# 04_POWER.net
KiCad netlist of a schematic drawn in Altium Designer
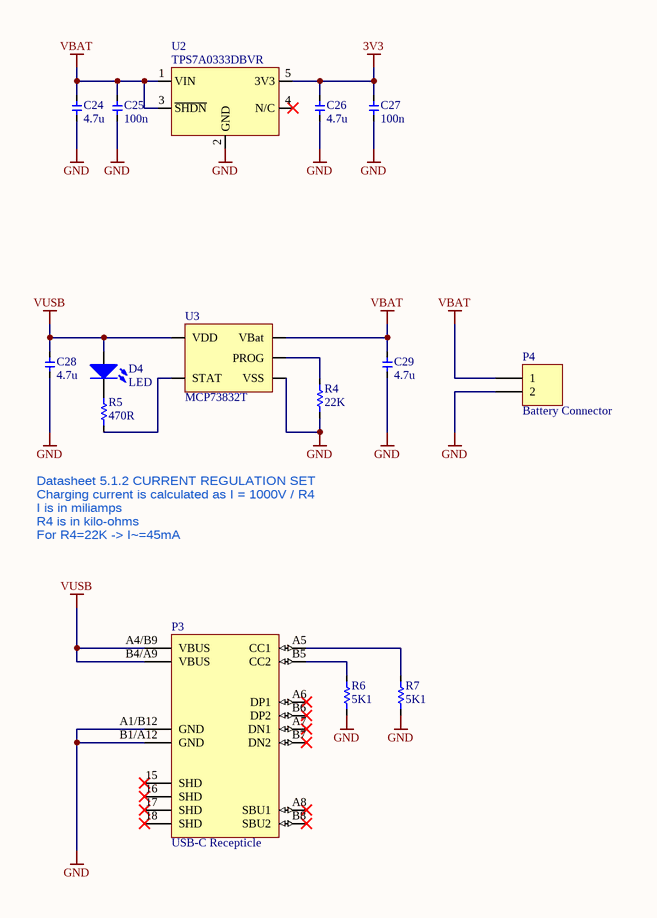
[diagram p0: 04_POWER.SchDoc]

(export (version "E")
  (design (tool "Eeschema 10.0.6"))
  (components
    (comp (ref "C24")
      (value "4.7u")
      (footprint "Moji Footprintovi:0603 - CAP HS")
      (description "Capacitor")
      (fields
        (field (name "MANUFACTURER") "Samsung Electro-Mechanics")
        (field (name "MANUFACTURER PART NUMBER") "CL10B475KQ8NQNC")
      )
      (libsource (lib "Moji Schematici (1)") (part "Cap"))
    )
    (comp (ref "C25")
      (value "100n")
      (footprint "Moji Footprintovi:0603 - CAP HS")
      (description "Capacitor")
      (fields
        (field (name "MANUFACTURER") "Samsung Electro-Mechanics")
        (field (name "MANUFACTURER PART NUMBER") "CL10B104KB8NNWC")
      )
      (libsource (lib "Moji Schematici (1)") (part "Cap"))
    )
    (comp (ref "C26")
      (value "4.7u")
      (footprint "Moji Footprintovi:0603 - CAP HS")
      (description "Capacitor")
      (fields
        (field (name "MANUFACTURER") "Samsung Electro-Mechanics")
        (field (name "MANUFACTURER PART NUMBER") "CL10B475KQ8NQNC")
      )
      (libsource (lib "Moji Schematici (1)") (part "Cap"))
    )
    (comp (ref "C27")
      (value "100n")
      (footprint "Moji Footprintovi:0603 - CAP HS")
      (description "Capacitor")
      (fields
        (field (name "MANUFACTURER") "Samsung Electro-Mechanics")
        (field (name "MANUFACTURER PART NUMBER") "CL10B104KB8NNWC")
      )
      (libsource (lib "Moji Schematici (1)") (part "Cap"))
    )
    (comp (ref "C28")
      (value "4.7u")
      (footprint "Moji Footprintovi:0603 - CAP HS")
      (description "Capacitor")
      (fields
        (field (name "MANUFACTURER") "Samsung Electro-Mechanics")
        (field (name "MANUFACTURER PART NUMBER") "CL10B475KQ8NQNC")
      )
      (libsource (lib "Moji Schematici (1)") (part "Cap"))
    )
    (comp (ref "C29")
      (value "4.7u")
      (footprint "Moji Footprintovi:0603 - CAP HS")
      (description "Capacitor")
      (fields
        (field (name "MANUFACTURER") "Samsung Electro-Mechanics")
        (field (name "MANUFACTURER PART NUMBER") "CL10B475KQ8NQNC")
      )
      (libsource (lib "Moji Schematici (1)") (part "Cap"))
    )
    (comp (ref "D4")
      (value "LED")
      (footprint "Footprint_Misc:0603 Diode")
      (description "Typical RED GaAs LED")
      (fields
        (field (name "DISTRIBUTOR PART NUMBER") "Lite-On Inc.")
        (field (name "MANUFACTURER PART NUMBER") "LTST-C193KRKT-5A")
      )
      (libsource (lib "Schematic_Misc") (part "LED"))
    )
    (comp (ref "P3")
      (value "USB-C Recepticle")
      (footprint "Footprint_Misc:GCT_USB4105-GF-A")
      (description "CONN RCPT USB2.0 TYPEC 5A")
      (fields (field (name "MANUFACTURER") "GCT") (field (name "MANUFACTURER PART NUMBER") "USB4105-GF-A"))
      (libsource (lib "Schematic_Misc") (part "USB-C Recepticle"))
    )
    (comp (ref "P4")
      (value "Battery Connector")
      (footprint "Footprint_Misc:Header 2x1 SMD")
      (description "Header, 2-Pin")
      (libsource (lib "Schematic_Misc") (part "Header 2"))
    )
    (comp (ref "R4")
      (value "22K")
      (footprint "Footprint_Misc:0603")
      (description "Resistor")
      (fields
        (field (name "DISTRIBUTOR PART NUMBER") "13-AC0603FR-1022KLCT-ND")
        (field (name "MANUFACTURER") "YAGEO")
      )
      (libsource (lib "Schematic_Misc") (part "Res"))
    )
    (comp (ref "R5")
      (value "470R")
      (footprint "Footprint_Misc:0603")
      (description "Resistor")
      (fields
        (field (name "DISTRIBUTOR PART NUMBER") "13-RC0603FR-10470RLCT-ND")
        (field (name "MANUFACTURER") "YAGEO")
      )
      (libsource (lib "Schematic_Misc") (part "Res"))
    )
    (comp (ref "R6")
      (value "5K1")
      (footprint "Footprint_Misc:0603")
      (description "Resistor")
      (fields
        (field (name "DISTRIBUTOR PART NUMBER") "13-RC0603FR-135K1LCT-ND")
        (field (name "MANUFACTURER") "YAGEO")
      )
      (libsource (lib "Schematic_Misc") (part "Res"))
    )
    (comp (ref "R7")
      (value "5K1")
      (footprint "Footprint_Misc:0603")
      (description "Resistor")
      (fields
        (field (name "DISTRIBUTOR PART NUMBER") "13-RC0603FR-135K1LCT-ND")
        (field (name "MANUFACTURER") "YAGEO")
      )
      (libsource (lib "Schematic_Misc") (part "Res"))
    )
    (comp (ref "U2")
      (value "TPS7A0333DBVR")
      (footprint "Moji Footprintovi:SOT-23-5")
      (description "Linear Voltage Regulator IC  1 Output  450mA SOT-23-5")
      (fields
        (field (name "DISTRIBUTOR PART NUMBER") "NCP161ASN330T1GOSCT-ND")
        (field (name "MANUFACTURER") "ON Semiconductor")
      )
      (libsource (lib "Schematic_Misc") (part "NCP161ASN330T1G"))
    )
    (comp (ref "U3")
      (value "MCP73832T")
      (footprint "Moji Footprintovi:SOT-23-5")
      (description "1xLi-Ion char, 0.5A, 4.2V reg, 3.75-6V")
      (fields
        (field (name "DISTRIBUTOR PART NUMBER") "MCP73832T-2ACI/OTCT-ND")
        (field (name "MANUFACTURER") "Microchip Technology")
      )
      (libsource (lib "Schematic_Misc") (part "MCP73832"))
    )
  )
  (nets
    (net (code "1") (name "3V3") (class "Default")
      (node (ref "C26") (pin "1") (pinfunction "1_1") (pintype "passive"))
      (node (ref "C27") (pin "1") (pinfunction "1_1") (pintype "passive"))
      (node (ref "U2") (pin "5") (pinfunction "3V3_5") (pintype "passive"))
    )
    (net (code "2") (name "GND") (class "Default")
      (node (ref "C24") (pin "2") (pinfunction "2_2") (pintype "passive"))
      (node (ref "C25") (pin "2") (pinfunction "2_2") (pintype "passive"))
      (node (ref "C26") (pin "2") (pinfunction "2_2") (pintype "passive"))
      (node (ref "C27") (pin "2") (pinfunction "2_2") (pintype "passive"))
      (node (ref "C28") (pin "2") (pinfunction "2_2") (pintype "passive"))
      (node (ref "C29") (pin "2") (pinfunction "2_2") (pintype "passive"))
      (node (ref "P3") (pin "A1/B12") (pinfunction "GND_A1/B12") (pintype "power_in"))
      (node (ref "P3") (pin "B1/A12") (pinfunction "GND_B1/A12") (pintype "power_in"))
      (node (ref "P4") (pin "2") (pinfunction "2_2") (pintype "passive"))
      (node (ref "R4") (pin "1") (pinfunction "1_1") (pintype "passive"))
      (node (ref "R6") (pin "1") (pinfunction "1_1") (pintype "passive"))
      (node (ref "R7") (pin "1") (pinfunction "1_1") (pintype "passive"))
      (node (ref "U2") (pin "2") (pinfunction "GND_2") (pintype "passive"))
      (node (ref "U3") (pin "2") (pinfunction "VSS_2") (pintype "passive"))
    )
    (net (code "3") (name "Net-(D4-PadK)") (class "Default")
      (node (ref "D4") (pin "K") (pinfunction "K_K") (pintype "passive"))
      (node (ref "R5") (pin "2") (pinfunction "2_2") (pintype "passive"))
    )
    (net (code "4") (name "Net-(P3-CC1)") (class "Default")
      (node (ref "P3") (pin "A5") (pinfunction "CC1_A5") (pintype "bidirectional"))
      (node (ref "R7") (pin "2") (pinfunction "2_2") (pintype "passive"))
    )
    (net (code "5") (name "Net-(P3-CC2)") (class "Default")
      (node (ref "P3") (pin "B5") (pinfunction "CC2_B5") (pintype "bidirectional"))
      (node (ref "R6") (pin "2") (pinfunction "2_2") (pintype "passive"))
    )
    (net (code "6") (name "Net-(U3-PROG)") (class "Default")
      (node (ref "R4") (pin "2") (pinfunction "2_2") (pintype "passive"))
      (node (ref "U3") (pin "5") (pinfunction "PROG_5") (pintype "passive"))
    )
    (net (code "7") (name "Net-(U3-STAT)") (class "Default")
      (node (ref "R5") (pin "1") (pinfunction "1_1") (pintype "passive"))
      (node (ref "U3") (pin "1") (pinfunction "STAT_1") (pintype "passive"))
    )
    (net (code "8") (name "VBAT") (class "Default")
      (node (ref "C24") (pin "1") (pinfunction "1_1") (pintype "passive"))
      (node (ref "C25") (pin "1") (pinfunction "1_1") (pintype "passive"))
      (node (ref "C29") (pin "1") (pinfunction "1_1") (pintype "passive"))
      (node (ref "P4") (pin "1") (pinfunction "1_1") (pintype "passive"))
      (node (ref "U2") (pin "1") (pinfunction "VIN_1") (pintype "passive"))
      (node (ref "U2") (pin "3") (pinfunction "~{SHDN}_3") (pintype "passive"))
      (node (ref "U3") (pin "3") (pinfunction "VBat_3") (pintype "passive"))
    )
    (net (code "9") (name "VUSB") (class "Default")
      (node (ref "C28") (pin "1") (pinfunction "1_1") (pintype "passive"))
      (node (ref "D4") (pin "A") (pinfunction "A_A") (pintype "passive"))
      (node (ref "P3") (pin "A4/B9") (pinfunction "VBUS_A4/B9") (pintype "power_in"))
      (node (ref "P3") (pin "B4/A9") (pinfunction "VBUS_B4/A9") (pintype "power_in"))
      (node (ref "U3") (pin "4") (pinfunction "VDD_4") (pintype "passive"))
    )
    (net (code "10") (name "unconnected-(P3-DN1-PadA7)") (class "Default")
      (node (ref "P3") (pin "A7") (pinfunction "DN1_A7") (pintype "bidirectional+no_connect"))
    )
    (net (code "11") (name "unconnected-(P3-DN2-PadB7)") (class "Default")
      (node (ref "P3") (pin "B7") (pinfunction "DN2_B7") (pintype "bidirectional+no_connect"))
    )
    (net (code "12") (name "unconnected-(P3-DP1-PadA6)") (class "Default")
      (node (ref "P3") (pin "A6") (pinfunction "DP1_A6") (pintype "bidirectional+no_connect"))
    )
    (net (code "13") (name "unconnected-(P3-DP2-PadB6)") (class "Default")
      (node (ref "P3") (pin "B6") (pinfunction "DP2_B6") (pintype "bidirectional+no_connect"))
    )
    (net (code "14") (name "unconnected-(P3-SBU1-PadA8)") (class "Default")
      (node (ref "P3") (pin "A8") (pinfunction "SBU1_A8") (pintype "bidirectional+no_connect"))
    )
    (net (code "15") (name "unconnected-(P3-SBU2-PadB8)") (class "Default")
      (node (ref "P3") (pin "B8") (pinfunction "SBU2_B8") (pintype "bidirectional+no_connect"))
    )
    (net (code "16") (name "unconnected-(P3-SHD-Pad15)") (class "Default")
      (node (ref "P3") (pin "15") (pinfunction "SHD_15") (pintype "power_in+no_connect"))
    )
    (net (code "17") (name "unconnected-(P3-SHD-Pad16)") (class "Default")
      (node (ref "P3") (pin "16") (pinfunction "SHD_16") (pintype "power_in+no_connect"))
    )
    (net (code "18") (name "unconnected-(P3-SHD-Pad17)") (class "Default")
      (node (ref "P3") (pin "17") (pinfunction "SHD_17") (pintype "power_in+no_connect"))
    )
    (net (code "19") (name "unconnected-(P3-SHD-Pad18)") (class "Default")
      (node (ref "P3") (pin "18") (pinfunction "SHD_18") (pintype "power_in+no_connect"))
    )
    (net (code "20") (name "unconnected-(U2-N{slash}C-Pad4)") (class "Default")
      (node (ref "U2") (pin "4") (pinfunction "N/C_4") (pintype "passive+no_connect"))
    )
  )
)
